# Module.net
KiCad netlist of a schematic drawn in Altium Designer
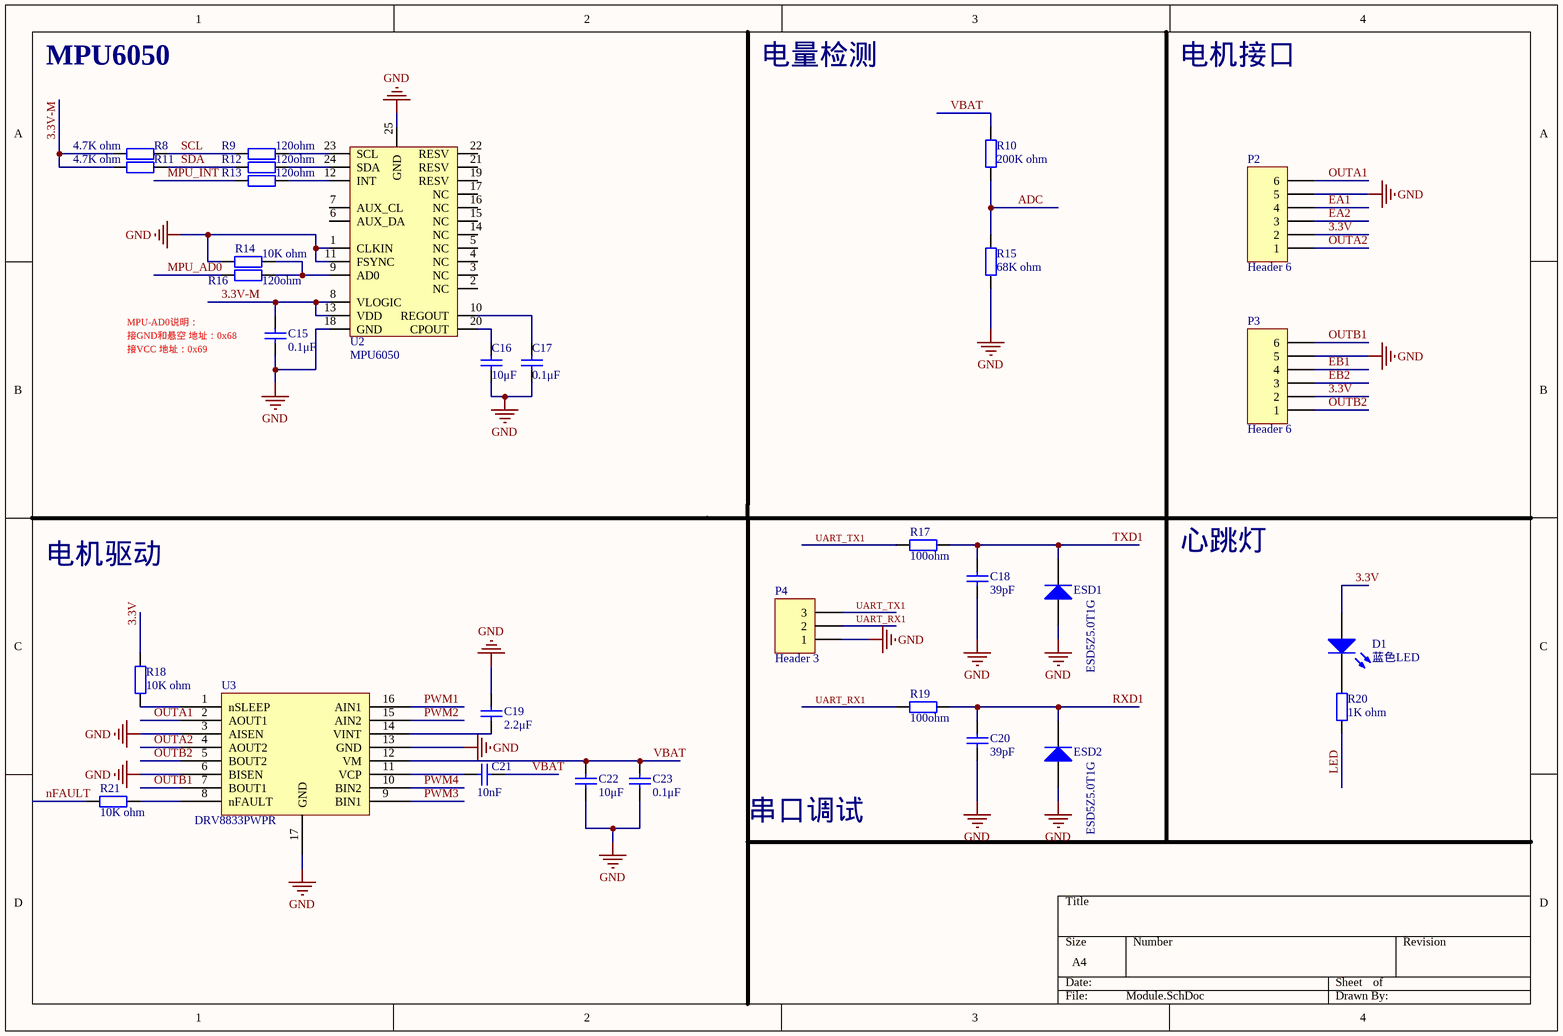
[diagram p0: Module.SchDoc]

(export (version "E")
  (design (tool "Eeschema 10.0.6"))
  (components
    (comp (ref "C15")
      (value "0.1μF")
      (footprint "0603C")
      (description "0.1μF_50V,X7R,±5%")
      (libsource (lib "Yang_Lib") (part "Cap_0.1μF_50V_0603"))
    )
    (comp (ref "C16")
      (value "10μF")
      (footprint "0603C")
      (description "10μF_35V,X5R,20%")
      (libsource (lib "Yang_Lib") (part "Cap_10μF_35V_0603"))
    )
    (comp (ref "C17")
      (value "0.1μF")
      (footprint "0603C")
      (description "0.1μF_50V,X7R,±5%")
      (libsource (lib "Yang_Lib") (part "Cap_0.1μF_50V_0603"))
    )
    (comp (ref "C18")
      (value "39pF")
      (footprint "0603C")
      (description "39pF_50V,C0G (EIA),±1%")
      (libsource (lib "Yang_Lib") (part "Cap_39pF_50V_0603"))
    )
    (comp (ref "C19")
      (value "2.2μF")
      (footprint "0603C")
      (description "2.2μF_35V,±10%")
      (libsource (lib "Yang_Lib") (part "Cap_2.2uF_35V_0603"))
    )
    (comp (ref "C20")
      (value "39pF")
      (footprint "0603C")
      (description "39pF_50V,C0G (EIA),±1%")
      (libsource (lib "Yang_Lib") (part "Cap_39pF_50V_0603"))
    )
    (comp (ref "C21")
      (value "10nF")
      (footprint "0603C")
      (description "10nF_50V,SL_0603,±5%")
      (libsource (lib "Yang_Lib") (part "Cap_10nF_50V_0603"))
    )
    (comp (ref "C22")
      (value "10μF")
      (footprint "0603C")
      (description "10μF_35V,X5R,20%")
      (libsource (lib "Yang_Lib") (part "Cap_10μF_35V_0603"))
    )
    (comp (ref "C23")
      (value "0.1μF")
      (footprint "0603C")
      (description "0.1μF_50V,X7R,±5%")
      (libsource (lib "Yang_Lib") (part "Cap_0.1μF_50V_0603"))
    )
    (comp (ref "D1")
      (value "蓝色LED")
      (footprint "Yang_Lib:0603LED")
      (libsource (lib "FSR_BodyLib") (part "蓝色LED"))
    )
    (comp (ref "ESD1")
      (value "ESD5Z5.0T1G")
      (footprint "SOD523")
      (libsource (lib "Yang_Lib") (part "ESD5Z5.0T1G_SOD523"))
    )
    (comp (ref "ESD2")
      (value "ESD5Z5.0T1G")
      (footprint "SOD523")
      (libsource (lib "Yang_Lib") (part "ESD5Z5.0T1G_SOD523"))
    )
    (comp (ref "P2")
      (value "Header 6")
      (footprint "HDR1X6")
      (description "Header, 6-Pin")
      (fields (field (name "PUBLISHER") "Altium Limited"))
      (libsource (lib "Miscellaneous Connectors") (part "Header 6"))
    )
    (comp (ref "P3")
      (value "Header 6")
      (footprint "HDR1X6")
      (description "Header, 6-Pin")
      (fields (field (name "PUBLISHER") "Altium Limited"))
      (libsource (lib "Miscellaneous Connectors") (part "Header 6"))
    )
    (comp (ref "P4")
      (value "Header 3")
      (footprint "HDR1X3")
      (description "Header, 3-Pin")
      (fields (field (name "PUBLISHER") "Altium Limited"))
      (libsource (lib "Miscellaneous Connectors") (part "Header 3"))
    )
    (comp (ref "R8")
      (value "4.7K ohm")
      (footprint "0603R")
      (description "4.7K ohm,1%")
      (libsource (lib "Yang_Lib") (part "Res_4.7K ohm_0603"))
    )
    (comp (ref "R9")
      (value "120ohm")
      (footprint "0603R")
      (description "120 ohm_5%")
      (libsource (lib "Yang_Lib") (part "Res_120ohm_0603"))
    )
    (comp (ref "R10")
      (value "200K ohm")
      (footprint "0603R")
      (description "200K ohm,1%")
      (libsource (lib "Yang_Lib") (part "Res_200K ohm_0603"))
    )
    (comp (ref "R11")
      (value "4.7K ohm")
      (footprint "0603R")
      (description "4.7K ohm,1%")
      (libsource (lib "Yang_Lib") (part "Res_4.7K ohm_0603"))
    )
    (comp (ref "R12")
      (value "120ohm")
      (footprint "0603R")
      (description "120 ohm_5%")
      (libsource (lib "Yang_Lib") (part "Res_120ohm_0603"))
    )
    (comp (ref "R13")
      (value "120ohm")
      (footprint "0603R")
      (description "120 ohm_5%")
      (libsource (lib "Yang_Lib") (part "Res_120ohm_0603"))
    )
    (comp (ref "R14")
      (value "10K ohm")
      (footprint "0603R")
      (description "10K ohm,1%")
      (libsource (lib "Yang_Lib") (part "Res_10K ohm_0603"))
    )
    (comp (ref "R15")
      (value "68K ohm")
      (footprint "0603R")
      (description "68K ohm,1%")
      (libsource (lib "Yang_Lib") (part "Res_68K ohm_0603"))
    )
    (comp (ref "R16")
      (value "120ohm")
      (footprint "0603R")
      (description "120 ohm_5%")
      (libsource (lib "Yang_Lib") (part "Res_120ohm_0603"))
    )
    (comp (ref "R17")
      (value "100ohm")
      (footprint "0603R")
      (description "100 ohm_5%")
      (libsource (lib "Yang_Lib") (part "Res_100ohm_0603"))
    )
    (comp (ref "R18")
      (value "10K ohm")
      (footprint "0603R")
      (description "10K ohm,1%")
      (libsource (lib "") (part "Res_10K ohm_0603_1"))
    )
    (comp (ref "R19")
      (value "100ohm")
      (footprint "0603R")
      (description "100 ohm_5%")
      (libsource (lib "Yang_Lib") (part "Res_100ohm_0603"))
    )
    (comp (ref "R20")
      (value "1K ohm")
      (footprint "0603R")
      (description "1K ohm,1%")
      (libsource (lib "Yang_Lib") (part "Res_1K ohm_0603"))
    )
    (comp (ref "R21")
      (value "10K ohm")
      (footprint "0603R")
      (description "10K ohm,1%")
      (libsource (lib "") (part "Res_10K ohm_0603_2"))
    )
    (comp (ref "U2") (value "MPU6050") (footprint "QFN24") (libsource (lib "Yang_Lib") (part "MPU6050")))
    (comp (ref "U3")
      (value "DRV8833PWPR")
      (footprint "TSSOP16")
      (libsource (lib "Yang_Lib") (part "DRV8833PWPR"))
    )
  )
  (nets
    (net (code "1") (name "/3.3V") (class "Default")
      (node (ref "D1") (pin "1") (pinfunction "A_1") (pintype "passive"))
      (node (ref "P2") (pin "2") (pinfunction "2_2") (pintype "passive"))
      (node (ref "P3") (pin "2") (pinfunction "2_2") (pintype "passive"))
      (node (ref "R18") (pin "2") (pinfunction "2_2") (pintype "passive"))
    )
    (net (code "2") (name "/3.3V-M") (class "Default")
      (node (ref "C15") (pin "2") (pinfunction "2_2") (pintype "passive"))
      (node (ref "R11") (pin "1") (pinfunction "1_1") (pintype "passive"))
      (node (ref "R8") (pin "1") (pinfunction "1_1") (pintype "passive"))
      (node (ref "U2") (pin "13") (pinfunction "VDD_13") (pintype "passive"))
      (node (ref "U2") (pin "8") (pinfunction "VLOGIC_8") (pintype "passive"))
    )
    (net (code "3") (name "/ADC") (class "Default")
      (node (ref "R10") (pin "1") (pinfunction "1_1") (pintype "passive"))
      (node (ref "R15") (pin "2") (pinfunction "2_2") (pintype "passive"))
    )
    (net (code "4") (name "/EA1") (class "Default")
      (node (ref "P2") (pin "4") (pinfunction "4_4") (pintype "passive"))
    )
    (net (code "5") (name "/EA2") (class "Default")
      (node (ref "P2") (pin "3") (pinfunction "3_3") (pintype "passive"))
    )
    (net (code "6") (name "/EB1") (class "Default")
      (node (ref "P3") (pin "4") (pinfunction "4_4") (pintype "passive"))
    )
    (net (code "7") (name "/EB2") (class "Default")
      (node (ref "P3") (pin "3") (pinfunction "3_3") (pintype "passive"))
    )
    (net (code "8") (name "/LED") (class "Default")
      (node (ref "R20") (pin "1") (pinfunction "1_1") (pintype "passive"))
    )
    (net (code "9") (name "/MPU_AD0") (class "Default")
      (node (ref "R16") (pin "1") (pinfunction "1_1") (pintype "passive"))
    )
    (net (code "10") (name "/MPU_INT") (class "Default")
      (node (ref "R13") (pin "1") (pinfunction "1_1") (pintype "passive"))
    )
    (net (code "11") (name "/OUTA1") (class "Default")
      (node (ref "P2") (pin "6") (pinfunction "6_6") (pintype "passive"))
      (node (ref "U3") (pin "2") (pinfunction "AOUT1_2") (pintype "passive"))
    )
    (net (code "12") (name "/OUTA2") (class "Default")
      (node (ref "P2") (pin "1") (pinfunction "1_1") (pintype "passive"))
      (node (ref "U3") (pin "4") (pinfunction "AOUT2_4") (pintype "passive"))
    )
    (net (code "13") (name "/OUTB1") (class "Default")
      (node (ref "P3") (pin "6") (pinfunction "6_6") (pintype "passive"))
      (node (ref "U3") (pin "7") (pinfunction "BOUT1_7") (pintype "passive"))
    )
    (net (code "14") (name "/OUTB2") (class "Default")
      (node (ref "P3") (pin "1") (pinfunction "1_1") (pintype "passive"))
      (node (ref "U3") (pin "5") (pinfunction "BOUT2_5") (pintype "passive"))
    )
    (net (code "15") (name "/PWM1") (class "Default")
      (node (ref "U3") (pin "16") (pinfunction "AIN1_16") (pintype "passive"))
    )
    (net (code "16") (name "/PWM2") (class "Default")
      (node (ref "U3") (pin "15") (pinfunction "AIN2_15") (pintype "passive"))
    )
    (net (code "17") (name "/PWM3") (class "Default")
      (node (ref "U3") (pin "9") (pinfunction "BIN1_9") (pintype "passive"))
    )
    (net (code "18") (name "/PWM4") (class "Default")
      (node (ref "U3") (pin "10") (pinfunction "BIN2_10") (pintype "passive"))
    )
    (net (code "19") (name "/RXD1") (class "Default")
      (node (ref "C20") (pin "2") (pinfunction "2_2") (pintype "passive"))
      (node (ref "ESD2") (pin "2") (pinfunction "K_2") (pintype "passive"))
      (node (ref "R19") (pin "2") (pinfunction "2_2") (pintype "passive"))
    )
    (net (code "20") (name "/SCL") (class "Default")
      (node (ref "R8") (pin "2") (pinfunction "2_2") (pintype "passive"))
      (node (ref "R9") (pin "1") (pinfunction "1_1") (pintype "passive"))
    )
    (net (code "21") (name "/SDA") (class "Default")
      (node (ref "R11") (pin "2") (pinfunction "2_2") (pintype "passive"))
      (node (ref "R12") (pin "1") (pinfunction "1_1") (pintype "passive"))
    )
    (net (code "22") (name "/TXD1") (class "Default")
      (node (ref "C18") (pin "2") (pinfunction "2_2") (pintype "passive"))
      (node (ref "ESD1") (pin "2") (pinfunction "K_2") (pintype "passive"))
      (node (ref "R17") (pin "2") (pinfunction "2_2") (pintype "passive"))
    )
    (net (code "23") (name "/UART_RX1") (class "Default")
      (node (ref "P4") (pin "2") (pinfunction "2_2") (pintype "passive"))
      (node (ref "R19") (pin "1") (pinfunction "1_1") (pintype "passive"))
    )
    (net (code "24") (name "/UART_TX1") (class "Default")
      (node (ref "P4") (pin "3") (pinfunction "3_3") (pintype "passive"))
      (node (ref "R17") (pin "1") (pinfunction "1_1") (pintype "passive"))
    )
    (net (code "25") (name "/VBAT") (class "Default")
      (node (ref "C21") (pin "2") (pinfunction "2_2") (pintype "passive"))
      (node (ref "C22") (pin "2") (pinfunction "2_2") (pintype "passive"))
      (node (ref "C23") (pin "2") (pinfunction "2_2") (pintype "passive"))
      (node (ref "R10") (pin "2") (pinfunction "2_2") (pintype "passive"))
      (node (ref "U3") (pin "12") (pinfunction "VM_12") (pintype "passive"))
    )
    (net (code "26") (name "/nFAULT") (class "Default")
      (node (ref "R21") (pin "2") (pinfunction "2_2") (pintype "passive"))
    )
    (net (code "27") (name "GND") (class "Default")
      (node (ref "C15") (pin "1") (pinfunction "1_1") (pintype "passive"))
      (node (ref "C16") (pin "1") (pinfunction "1_1") (pintype "passive"))
      (node (ref "C17") (pin "1") (pinfunction "1_1") (pintype "passive"))
      (node (ref "C18") (pin "1") (pinfunction "1_1") (pintype "passive"))
      (node (ref "C19") (pin "2") (pinfunction "2_2") (pintype "passive"))
      (node (ref "C20") (pin "1") (pinfunction "1_1") (pintype "passive"))
      (node (ref "C22") (pin "1") (pinfunction "1_1") (pintype "passive"))
      (node (ref "C23") (pin "1") (pinfunction "1_1") (pintype "passive"))
      (node (ref "ESD1") (pin "1") (pinfunction "A_1") (pintype "passive"))
      (node (ref "ESD2") (pin "1") (pinfunction "A_1") (pintype "passive"))
      (node (ref "P2") (pin "5") (pinfunction "5_5") (pintype "passive"))
      (node (ref "P3") (pin "5") (pinfunction "5_5") (pintype "passive"))
      (node (ref "P4") (pin "1") (pinfunction "1_1") (pintype "passive"))
      (node (ref "R14") (pin "1") (pinfunction "1_1") (pintype "passive"))
      (node (ref "R15") (pin "1") (pinfunction "1_1") (pintype "passive"))
      (node (ref "U2") (pin "1") (pinfunction "CLKIN_1") (pintype "passive"))
      (node (ref "U2") (pin "11") (pinfunction "FSYNC_11") (pintype "passive"))
      (node (ref "U2") (pin "18") (pinfunction "GND_18") (pintype "passive"))
      (node (ref "U2") (pin "25") (pinfunction "GND_25") (pintype "passive"))
      (node (ref "U3") (pin "13") (pinfunction "GND_13") (pintype "passive"))
      (node (ref "U3") (pin "17") (pinfunction "GND_17") (pintype "passive"))
      (node (ref "U3") (pin "3") (pinfunction "AISEN_3") (pintype "passive"))
      (node (ref "U3") (pin "6") (pinfunction "BISEN_6") (pintype "passive"))
    )
    (net (code "28") (name "Net-(D1-K)") (class "Default")
      (node (ref "D1") (pin "2") (pinfunction "K_2") (pintype "passive"))
      (node (ref "R20") (pin "2") (pinfunction "2_2") (pintype "passive"))
    )
    (net (code "29") (name "Net-(U2-AD0)") (class "Default")
      (node (ref "R14") (pin "2") (pinfunction "2_2") (pintype "passive"))
      (node (ref "R16") (pin "2") (pinfunction "2_2") (pintype "passive"))
      (node (ref "U2") (pin "9") (pinfunction "AD0_9") (pintype "passive"))
    )
    (net (code "30") (name "Net-(U2-CPOUT)") (class "Default")
      (node (ref "C16") (pin "2") (pinfunction "2_2") (pintype "passive"))
      (node (ref "U2") (pin "20") (pinfunction "CPOUT_20") (pintype "passive"))
    )
    (net (code "31") (name "Net-(U2-INT)") (class "Default")
      (node (ref "R13") (pin "2") (pinfunction "2_2") (pintype "passive"))
      (node (ref "U2") (pin "12") (pinfunction "INT_12") (pintype "passive"))
    )
    (net (code "32") (name "Net-(U2-REGOUT)") (class "Default")
      (node (ref "C17") (pin "2") (pinfunction "2_2") (pintype "passive"))
      (node (ref "U2") (pin "10") (pinfunction "REGOUT_10") (pintype "passive"))
    )
    (net (code "33") (name "Net-(U2-SCL)") (class "Default")
      (node (ref "R9") (pin "2") (pinfunction "2_2") (pintype "passive"))
      (node (ref "U2") (pin "23") (pinfunction "SCL_23") (pintype "passive"))
    )
    (net (code "34") (name "Net-(U2-SDA)") (class "Default")
      (node (ref "R12") (pin "2") (pinfunction "2_2") (pintype "passive"))
      (node (ref "U2") (pin "24") (pinfunction "SDA_24") (pintype "passive"))
    )
    (net (code "35") (name "Net-(U3-VCP)") (class "Default")
      (node (ref "C21") (pin "1") (pinfunction "1_1") (pintype "passive"))
      (node (ref "U3") (pin "11") (pinfunction "VCP_11") (pintype "passive"))
    )
    (net (code "36") (name "Net-(U3-VINT)") (class "Default")
      (node (ref "C19") (pin "1") (pinfunction "1_1") (pintype "passive"))
      (node (ref "U3") (pin "14") (pinfunction "VINT_14") (pintype "passive"))
    )
    (net (code "37") (name "Net-(U3-nFAULT)") (class "Default")
      (node (ref "R21") (pin "1") (pinfunction "1_1") (pintype "passive"))
      (node (ref "U3") (pin "8") (pinfunction "nFAULT_8") (pintype "passive"))
    )
    (net (code "38") (name "Net-(U3-nSLEEP)") (class "Default")
      (node (ref "R18") (pin "1") (pinfunction "1_1") (pintype "passive"))
      (node (ref "U3") (pin "1") (pinfunction "nSLEEP_1") (pintype "passive"))
    )
    (net (code "39") (name "unconnected-(U2-AUX_CL-Pad7)") (class "Default")
      (node (ref "U2") (pin "7") (pinfunction "AUX_CL_7") (pintype "passive"))
    )
    (net (code "40") (name "unconnected-(U2-AUX_DA-Pad6)") (class "Default")
      (node (ref "U2") (pin "6") (pinfunction "AUX_DA_6") (pintype "passive"))
    )
    (net (code "41") (name "unconnected-(U2-NC-Pad2)") (class "Default")
      (node (ref "U2") (pin "2") (pinfunction "NC_2") (pintype "passive"))
    )
    (net (code "42") (name "unconnected-(U2-NC-Pad3)") (class "Default")
      (node (ref "U2") (pin "3") (pinfunction "NC_3") (pintype "passive"))
    )
    (net (code "43") (name "unconnected-(U2-NC-Pad4)") (class "Default")
      (node (ref "U2") (pin "4") (pinfunction "NC_4") (pintype "passive"))
    )
    (net (code "44") (name "unconnected-(U2-NC-Pad5)") (class "Default")
      (node (ref "U2") (pin "5") (pinfunction "NC_5") (pintype "passive"))
    )
    (net (code "45") (name "unconnected-(U2-NC-Pad14)") (class "Default")
      (node (ref "U2") (pin "14") (pinfunction "NC_14") (pintype "passive"))
    )
    (net (code "46") (name "unconnected-(U2-NC-Pad15)") (class "Default")
      (node (ref "U2") (pin "15") (pinfunction "NC_15") (pintype "passive"))
    )
    (net (code "47") (name "unconnected-(U2-NC-Pad16)") (class "Default")
      (node (ref "U2") (pin "16") (pinfunction "NC_16") (pintype "passive"))
    )
    (net (code "48") (name "unconnected-(U2-NC-Pad17)") (class "Default")
      (node (ref "U2") (pin "17") (pinfunction "NC_17") (pintype "passive"))
    )
    (net (code "49") (name "unconnected-(U2-RESV-Pad19)") (class "Default")
      (node (ref "U2") (pin "19") (pinfunction "RESV_19") (pintype "passive"))
    )
    (net (code "50") (name "unconnected-(U2-RESV-Pad21)") (class "Default")
      (node (ref "U2") (pin "21") (pinfunction "RESV_21") (pintype "passive"))
    )
    (net (code "51") (name "unconnected-(U2-RESV-Pad22)") (class "Default")
      (node (ref "U2") (pin "22") (pinfunction "RESV_22") (pintype "passive"))
    )
  )
)
